# CPS_Breakout.net
KiCad netlist of a schematic drawn in EAGLE
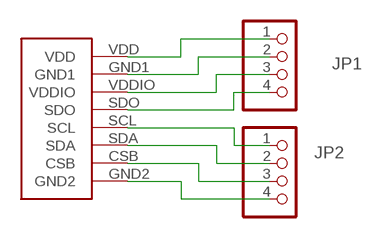
[diagram p0: schematic, sheet 1]

(export (version "E")
  (design (tool "Eeschema 10.0.6"))
  (components
    (comp (ref "B1")
      (value "CPS123")
      (footprint "eagle-import:CPS123")
      (libsource (lib "eagle-import") (part "CPS123"))
    )
    (comp (ref "JP1")
      (value "PINHD-1X4")
      (footprint "eagle-import:1X04")
      (libsource (lib "eagle-import") (part "PINHD-1X4"))
    )
    (comp (ref "JP2")
      (value "PINHD-1X4")
      (footprint "eagle-import:1X04")
      (libsource (lib "eagle-import") (part "PINHD-1X4"))
    )
  )
  (nets
    (net (code "1") (name "Net-(B1-PadCSB)") (class "Default")
      (node (ref "B1") (pin "CSB") (pinfunction "CSB_CSB") (pintype "bidirectional"))
      (node (ref "JP2") (pin "3") (pinfunction "3_3") (pintype "passive"))
    )
    (net (code "2") (name "Net-(B1-PadGND1)") (class "Default")
      (node (ref "B1") (pin "GND1") (pinfunction "GND1_GND1") (pintype "bidirectional"))
      (node (ref "JP1") (pin "2") (pinfunction "2_2") (pintype "passive"))
    )
    (net (code "3") (name "Net-(B1-PadGND2)") (class "Default")
      (node (ref "B1") (pin "GND2") (pinfunction "GND2_GND2") (pintype "bidirectional"))
      (node (ref "JP2") (pin "4") (pinfunction "4_4") (pintype "passive"))
    )
    (net (code "4") (name "Net-(B1-PadSCL)") (class "Default")
      (node (ref "B1") (pin "SCL") (pinfunction "SCL_SCL") (pintype "bidirectional"))
      (node (ref "JP2") (pin "1") (pinfunction "1_1") (pintype "passive"))
    )
    (net (code "5") (name "Net-(B1-PadSDA)") (class "Default")
      (node (ref "B1") (pin "SDA") (pinfunction "SDA_SDA") (pintype "bidirectional"))
      (node (ref "JP2") (pin "2") (pinfunction "2_2") (pintype "passive"))
    )
    (net (code "6") (name "Net-(B1-PadSDO)") (class "Default")
      (node (ref "B1") (pin "SDO") (pinfunction "SDO_SDO") (pintype "bidirectional"))
      (node (ref "JP1") (pin "4") (pinfunction "4_4") (pintype "passive"))
    )
    (net (code "7") (name "Net-(B1-PadVDD)") (class "Default")
      (node (ref "B1") (pin "VDD") (pinfunction "VDD_VDD") (pintype "bidirectional"))
      (node (ref "JP1") (pin "1") (pinfunction "1_1") (pintype "passive"))
    )
    (net (code "8") (name "Net-(B1-PadVDDIO)") (class "Default")
      (node (ref "B1") (pin "VDDIO") (pinfunction "VDDIO_VDDIO") (pintype "bidirectional"))
      (node (ref "JP1") (pin "3") (pinfunction "3_3") (pintype "passive"))
    )
  )
)
